# MB1297_Peripherals.net
KiCad netlist of a schematic drawn in Altium Designer
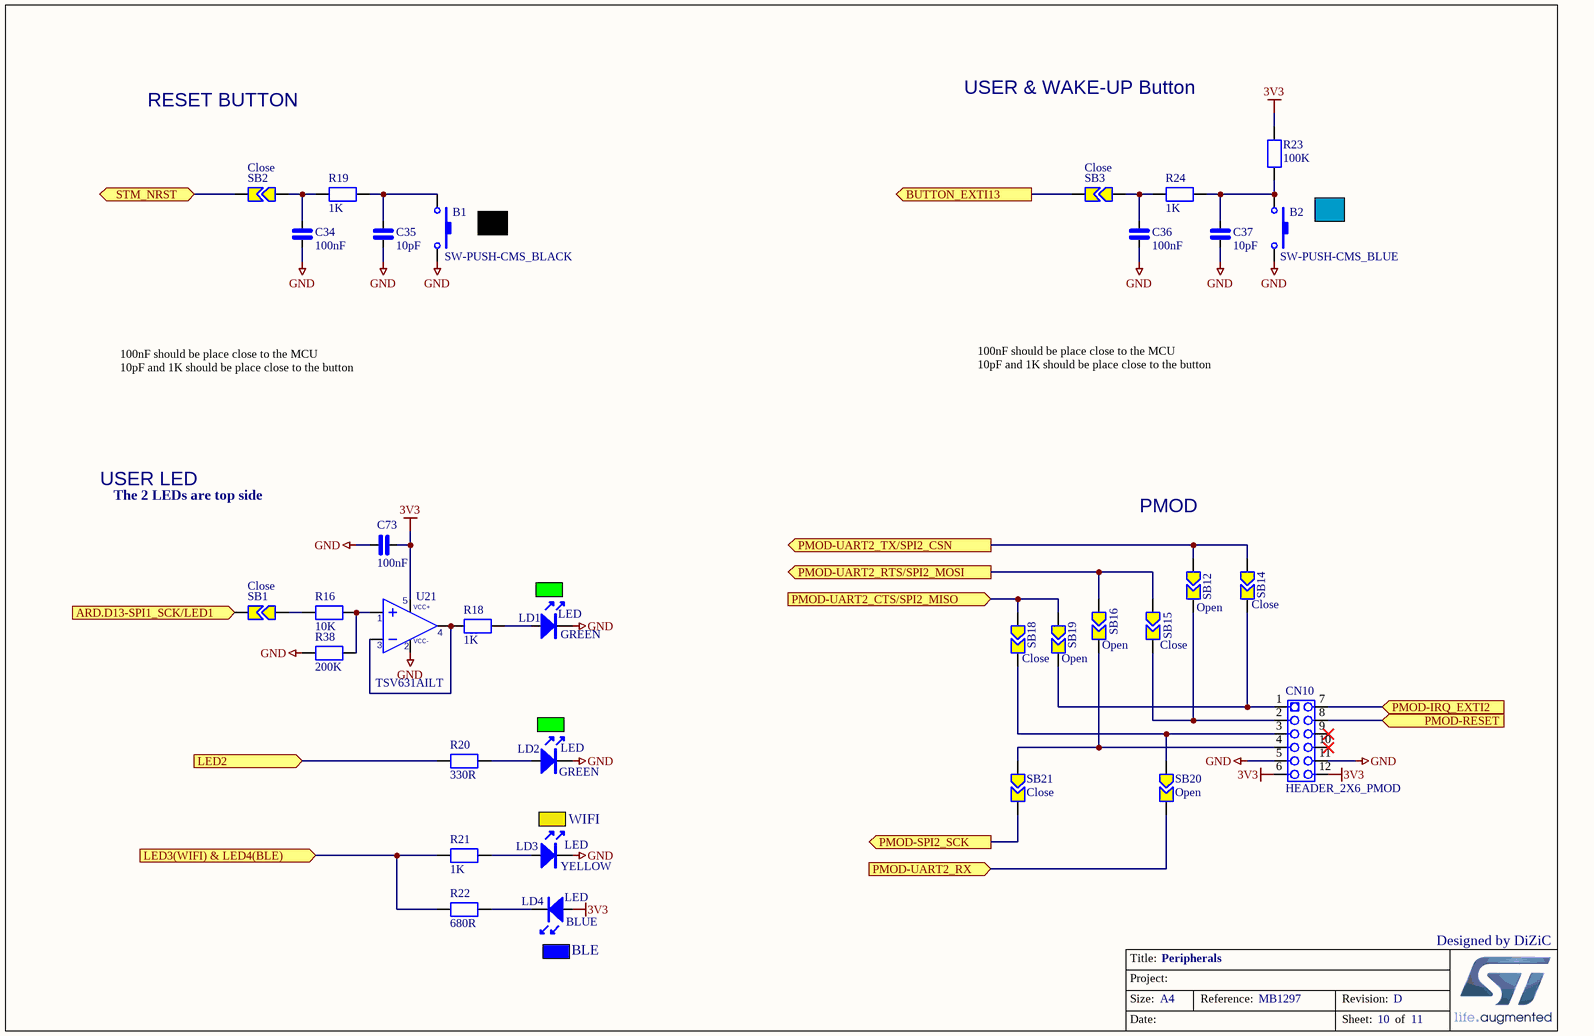
[diagram p0: MB1297_Peripherals.SchDoc]

(export (version "E")
  (design (tool "Eeschema 10.0.6"))
  (components
    (comp (ref "B1")
      (value "SW-PUSH-CMS_BLACK")
      (footprint "SWI_WEALTHMETAL_TD-0341_4P - BACK")
      (description "Push-button SMD")
      (libsource (lib "ST_Lib3D") (part "SW-PB_2"))
    )
    (comp (ref "B2")
      (value "SW-PUSH-CMS_BLUE")
      (footprint "SWI_WEALTHMETAL_TD-0341_4P - BLUE")
      (description "Push-button SMD")
      (libsource (lib "ST_Lib3D") (part "SW-PB_2"))
    )
    (comp (ref "C34")
      (value "100nF")
      (footprint "0402_CAP_NPOL")
      (description "Capacitor_not polarized")
      (libsource (lib "ST_Lib3D") (part "CAP_NPOL"))
    )
    (comp (ref "C35")
      (value "10pF")
      (footprint "0402_CAP_NPOL")
      (description "Capacitor_not polarized")
      (libsource (lib "ST_Lib3D") (part "CAP_NPOL"))
    )
    (comp (ref "C36")
      (value "100nF")
      (footprint "0402_CAP_NPOL")
      (description "Capacitor_not polarized")
      (libsource (lib "ST_Lib3D") (part "CAP_NPOL"))
    )
    (comp (ref "C37")
      (value "10pF")
      (footprint "0402_CAP_NPOL")
      (description "Capacitor_not polarized")
      (libsource (lib "ST_Lib3D") (part "CAP_NPOL"))
    )
    (comp (ref "C73")
      (value "100nF")
      (footprint "0402_CAP_NPOL")
      (description "Capacitor_not polarized")
      (libsource (lib "ST_Lib3D") (part "CAP_NPOL"))
    )
    (comp (ref "CN10")
      (value "HEADER_2X6_PMOD")
      (footprint "Header F 2x6x2.54 TH H PMOD")
      (description "PMOD Connector Warning Specific Pinout")
      (libsource (lib "ST_Lib3D") (part "HEADER_2X6_PMOD"))
    )
    (comp (ref "LD1")
      (value "LED")
      (footprint "0603_LED_GREEN")
      (description "Light-Emitting Diode")
      (fields (field (name "COLOR") "GREEN"))
      (libsource (lib "ST_Lib3D") (part "LED"))
    )
    (comp (ref "LD2")
      (value "LED")
      (footprint "0603_LED_GREEN")
      (description "Light-Emitting Diode")
      (fields (field (name "COLOR") "GREEN"))
      (libsource (lib "ST_Lib3D") (part "LED"))
    )
    (comp (ref "LD3")
      (value "LED")
      (footprint "0603_LED_Yellow")
      (description "Light-Emitting Diode")
      (fields (field (name "COLOR") "YELLOW"))
      (libsource (lib "ST_Lib3D") (part "LED"))
    )
    (comp (ref "LD4")
      (value "LED")
      (footprint "0603_LED_Blue")
      (description "Light-Emitting Diode")
      (fields (field (name "COLOR") "BLUE"))
      (libsource (lib "ST_Lib3D") (part "LED"))
    )
    (comp (ref "R16")
      (value "10K")
      (footprint "0402_RES")
      (description "Resistor")
      (libsource (lib "Lib3D_Altium10_Schlib") (part "RES"))
    )
    (comp (ref "R18")
      (value "1K")
      (footprint "0402_RES")
      (description "Resistor")
      (libsource (lib "Lib3D_Altium10_Schlib") (part "RES"))
    )
    (comp (ref "R19")
      (value "1K")
      (footprint "0402_RES")
      (description "Resistor")
      (libsource (lib "Lib3D_Altium10_Schlib") (part "RES"))
    )
    (comp (ref "R20")
      (value "330R")
      (footprint "0402_RES")
      (description "Resistor")
      (libsource (lib "Lib3D_Altium10_Schlib") (part "RES"))
    )
    (comp (ref "R21")
      (value "1K")
      (footprint "0402_RES")
      (description "Resistor")
      (libsource (lib "Lib3D_Altium10_Schlib") (part "RES"))
    )
    (comp (ref "R22")
      (value "680R")
      (footprint "0402_RES")
      (description "Resistor")
      (libsource (lib "Lib3D_Altium10_Schlib") (part "RES"))
    )
    (comp (ref "R23")
      (value "100K")
      (footprint "0402_RES")
      (description "Resistor")
      (libsource (lib "Lib3D_Altium10_Schlib") (part "RES"))
    )
    (comp (ref "R24")
      (value "1K")
      (footprint "0402_RES")
      (description "Resistor")
      (libsource (lib "Lib3D_Altium10_Schlib") (part "RES"))
    )
    (comp (ref "R38")
      (value "200K")
      (footprint "0402_RES")
      (description "Resistor")
      (libsource (lib "Lib3D_Altium10_Schlib") (part "RES"))
    )
    (comp (ref "SB1")
      (value "Close")
      (footprint "SB")
      (description "Solder Jumper")
      (fields (field (name "PUBLISHER") "Altium Limited"))
      (libsource (lib "Lib3D_Altium10_Schlib") (part "Strap2"))
    )
    (comp (ref "SB2")
      (value "Close")
      (footprint "SB")
      (description "Solder Jumper")
      (fields (field (name "PUBLISHER") "Altium Limited"))
      (libsource (lib "Lib3D_Altium10_Schlib") (part "Strap2"))
    )
    (comp (ref "SB3")
      (value "Close")
      (footprint "SB")
      (description "Solder Jumper")
      (fields (field (name "PUBLISHER") "Altium Limited"))
      (libsource (lib "Lib3D_Altium10_Schlib") (part "Strap2"))
    )
    (comp (ref "SB12")
      (value "Open")
      (footprint "SB")
      (description "Solder Jumper")
      (fields (field (name "PUBLISHER") "Altium Limited"))
      (libsource (lib "Lib3D_Altium10_Schlib") (part "Strap2"))
    )
    (comp (ref "SB14")
      (value "Close")
      (footprint "SB")
      (description "Solder Jumper")
      (fields (field (name "PUBLISHER") "Altium Limited"))
      (libsource (lib "Lib3D_Altium10_Schlib") (part "Strap2"))
    )
    (comp (ref "SB15")
      (value "Close")
      (footprint "SB")
      (description "Solder Jumper")
      (fields (field (name "PUBLISHER") "Altium Limited"))
      (libsource (lib "Lib3D_Altium10_Schlib") (part "Strap2"))
    )
    (comp (ref "SB16")
      (value "Open")
      (footprint "SB")
      (description "Solder Jumper")
      (fields (field (name "PUBLISHER") "Altium Limited"))
      (libsource (lib "Lib3D_Altium10_Schlib") (part "Strap2"))
    )
    (comp (ref "SB18")
      (value "Close")
      (footprint "SB")
      (description "Solder Jumper")
      (fields (field (name "PUBLISHER") "Altium Limited"))
      (libsource (lib "Lib3D_Altium10_Schlib") (part "Strap2"))
    )
    (comp (ref "SB19")
      (value "Open")
      (footprint "SB")
      (description "Solder Jumper")
      (fields (field (name "PUBLISHER") "Altium Limited"))
      (libsource (lib "Lib3D_Altium10_Schlib") (part "Strap2"))
    )
    (comp (ref "SB20")
      (value "Open")
      (footprint "SB")
      (description "Solder Jumper")
      (fields (field (name "PUBLISHER") "Altium Limited"))
      (libsource (lib "Lib3D_Altium10_Schlib") (part "Strap2"))
    )
    (comp (ref "SB21")
      (value "Close")
      (footprint "SB")
      (description "Solder Jumper")
      (fields (field (name "PUBLISHER") "Altium Limited"))
      (libsource (lib "Lib3D_Altium10_Schlib") (part "Strap2"))
    )
    (comp (ref "U21")
      (value "TSV631AILT")
      (footprint "ST_Lib3D:SOT23-5")
      (description "TSV631AILT  Rail-to-rail input/output, 60 µA, 880 kHz, 5 V CMOS  operational amplifiers")
      (libsource (lib "ST_Lib3D") (part "TSV631AILT"))
    )
  )
  (nets
    (net (code "1") (name "/ARD.D13-SPI1_SCK{slash}LED1") (class "Default")
      (node (ref "SB1") (pin "1") (pinfunction "1_1") (pintype "passive"))
    )
    (net (code "2") (name "/BUTTON_EXTI13") (class "Default")
      (node (ref "SB3") (pin "1") (pinfunction "1_1") (pintype "passive"))
    )
    (net (code "3") (name "/LED2") (class "Default")
      (node (ref "R20") (pin "1") (pinfunction "1_1") (pintype "passive"))
    )
    (net (code "4") (name "/LED3(WIFI) & LED4(BLE)") (class "Default")
      (node (ref "R21") (pin "1") (pinfunction "1_1") (pintype "passive"))
      (node (ref "R22") (pin "1") (pinfunction "1_1") (pintype "passive"))
    )
    (net (code "5") (name "/PMOD-IRQ_EXTI2") (class "Default")
      (node (ref "CN10") (pin "7") (pinfunction "7_7") (pintype "passive"))
    )
    (net (code "6") (name "/PMOD-RESET") (class "Default")
      (node (ref "CN10") (pin "8") (pinfunction "8_8") (pintype "passive"))
    )
    (net (code "7") (name "/PMOD-SPI2_SCK") (class "Default")
      (node (ref "SB21") (pin "1") (pinfunction "1_1") (pintype "passive"))
    )
    (net (code "8") (name "/PMOD-UART2_CTS{slash}SPI2_MISO") (class "Default")
      (node (ref "SB18") (pin "2") (pinfunction "2_2") (pintype "passive"))
      (node (ref "SB19") (pin "2") (pinfunction "2_2") (pintype "passive"))
    )
    (net (code "9") (name "/PMOD-UART2_RTS{slash}SPI2_MOSI") (class "Default")
      (node (ref "SB15") (pin "2") (pinfunction "2_2") (pintype "passive"))
      (node (ref "SB16") (pin "2") (pinfunction "2_2") (pintype "passive"))
    )
    (net (code "10") (name "/PMOD-UART2_RX") (class "Default")
      (node (ref "SB20") (pin "1") (pinfunction "1_1") (pintype "passive"))
    )
    (net (code "11") (name "/PMOD-UART2_TX{slash}SPI2_CSN") (class "Default")
      (node (ref "SB12") (pin "2") (pinfunction "2_2") (pintype "passive"))
      (node (ref "SB14") (pin "2") (pinfunction "2_2") (pintype "passive"))
    )
    (net (code "12") (name "/STM_NRST") (class "Default")
      (node (ref "SB2") (pin "1") (pinfunction "1_1") (pintype "passive"))
    )
    (net (code "13") (name "3V3") (class "Default")
      (node (ref "C73") (pin "1") (pinfunction "1_1") (pintype "passive"))
      (node (ref "CN10") (pin "12") (pinfunction "12_12") (pintype "passive"))
      (node (ref "CN10") (pin "6") (pinfunction "6_6") (pintype "passive"))
      (node (ref "LD4") (pin "A") (pinfunction "A_A") (pintype "passive"))
      (node (ref "R23") (pin "2") (pinfunction "2_2") (pintype "passive"))
      (node (ref "U21") (pin "5") (pinfunction "V+_5") (pintype "passive"))
    )
    (net (code "14") (name "GND") (class "Default")
      (node (ref "B1") (pin "2") (pinfunction "2_2") (pintype "passive"))
      (node (ref "B2") (pin "2") (pinfunction "2_2") (pintype "passive"))
      (node (ref "C34") (pin "2") (pinfunction "2_2") (pintype "passive"))
      (node (ref "C35") (pin "2") (pinfunction "2_2") (pintype "passive"))
      (node (ref "C36") (pin "2") (pinfunction "2_2") (pintype "passive"))
      (node (ref "C37") (pin "2") (pinfunction "2_2") (pintype "passive"))
      (node (ref "C73") (pin "2") (pinfunction "2_2") (pintype "passive"))
      (node (ref "CN10") (pin "11") (pinfunction "11_11") (pintype "passive"))
      (node (ref "CN10") (pin "5") (pinfunction "5_5") (pintype "passive"))
      (node (ref "LD1") (pin "K") (pinfunction "K_K") (pintype "passive"))
      (node (ref "LD2") (pin "K") (pinfunction "K_K") (pintype "passive"))
      (node (ref "LD3") (pin "K") (pinfunction "K_K") (pintype "passive"))
      (node (ref "R38") (pin "1") (pinfunction "1_1") (pintype "passive"))
      (node (ref "U21") (pin "2") (pinfunction "V-_2") (pintype "passive"))
    )
    (net (code "15") (name "Net-(B1-Pad1)") (class "Default")
      (node (ref "B1") (pin "1") (pinfunction "1_1") (pintype "passive"))
      (node (ref "C35") (pin "1") (pinfunction "1_1") (pintype "passive"))
      (node (ref "R19") (pin "2") (pinfunction "2_2") (pintype "passive"))
    )
    (net (code "16") (name "Net-(B2-Pad1)") (class "Default")
      (node (ref "B2") (pin "1") (pinfunction "1_1") (pintype "passive"))
      (node (ref "C37") (pin "1") (pinfunction "1_1") (pintype "passive"))
      (node (ref "R23") (pin "1") (pinfunction "1_1") (pintype "passive"))
      (node (ref "R24") (pin "2") (pinfunction "2_2") (pintype "passive"))
    )
    (net (code "17") (name "Net-(C34-Pad1)") (class "Default")
      (node (ref "C34") (pin "1") (pinfunction "1_1") (pintype "passive"))
      (node (ref "R19") (pin "1") (pinfunction "1_1") (pintype "passive"))
      (node (ref "SB2") (pin "2") (pinfunction "2_2") (pintype "passive"))
    )
    (net (code "18") (name "Net-(C36-Pad1)") (class "Default")
      (node (ref "C36") (pin "1") (pinfunction "1_1") (pintype "passive"))
      (node (ref "R24") (pin "1") (pinfunction "1_1") (pintype "passive"))
      (node (ref "SB3") (pin "2") (pinfunction "2_2") (pintype "passive"))
    )
    (net (code "19") (name "Net-(CN10-Pad1)") (class "Default")
      (node (ref "CN10") (pin "1") (pinfunction "1_1") (pintype "passive"))
      (node (ref "SB14") (pin "1") (pinfunction "1_1") (pintype "passive"))
      (node (ref "SB19") (pin "1") (pinfunction "1_1") (pintype "passive"))
    )
    (net (code "20") (name "Net-(CN10-Pad2)") (class "Default")
      (node (ref "CN10") (pin "2") (pinfunction "2_2") (pintype "passive"))
      (node (ref "SB12") (pin "1") (pinfunction "1_1") (pintype "passive"))
      (node (ref "SB15") (pin "1") (pinfunction "1_1") (pintype "passive"))
    )
    (net (code "21") (name "Net-(CN10-Pad3)") (class "Default")
      (node (ref "CN10") (pin "3") (pinfunction "3_3") (pintype "passive"))
      (node (ref "SB18") (pin "1") (pinfunction "1_1") (pintype "passive"))
      (node (ref "SB20") (pin "2") (pinfunction "2_2") (pintype "passive"))
    )
    (net (code "22") (name "Net-(CN10-Pad4)") (class "Default")
      (node (ref "CN10") (pin "4") (pinfunction "4_4") (pintype "passive"))
      (node (ref "SB16") (pin "1") (pinfunction "1_1") (pintype "passive"))
      (node (ref "SB21") (pin "2") (pinfunction "2_2") (pintype "passive"))
    )
    (net (code "23") (name "Net-(LD1-PadA)") (class "Default")
      (node (ref "LD1") (pin "A") (pinfunction "A_A") (pintype "passive"))
      (node (ref "R18") (pin "2") (pinfunction "2_2") (pintype "passive"))
    )
    (net (code "24") (name "Net-(LD2-PadA)") (class "Default")
      (node (ref "LD2") (pin "A") (pinfunction "A_A") (pintype "passive"))
      (node (ref "R20") (pin "2") (pinfunction "2_2") (pintype "passive"))
    )
    (net (code "25") (name "Net-(LD3-PadA)") (class "Default")
      (node (ref "LD3") (pin "A") (pinfunction "A_A") (pintype "passive"))
      (node (ref "R21") (pin "2") (pinfunction "2_2") (pintype "passive"))
    )
    (net (code "26") (name "Net-(LD4-PadK)") (class "Default")
      (node (ref "LD4") (pin "K") (pinfunction "K_K") (pintype "passive"))
      (node (ref "R22") (pin "2") (pinfunction "2_2") (pintype "passive"))
    )
    (net (code "27") (name "Net-(R16-Pad1)") (class "Default")
      (node (ref "R16") (pin "1") (pinfunction "1_1") (pintype "passive"))
      (node (ref "SB1") (pin "2") (pinfunction "2_2") (pintype "passive"))
    )
    (net (code "28") (name "Net-(U21-IN+)") (class "Default")
      (node (ref "R16") (pin "2") (pinfunction "2_2") (pintype "passive"))
      (node (ref "R38") (pin "2") (pinfunction "2_2") (pintype "passive"))
      (node (ref "U21") (pin "1") (pinfunction "IN+_1") (pintype "passive"))
    )
    (net (code "29") (name "Net-(U21-IN-)") (class "Default")
      (node (ref "R18") (pin "1") (pinfunction "1_1") (pintype "passive"))
      (node (ref "U21") (pin "3") (pinfunction "IN-_3") (pintype "passive"))
      (node (ref "U21") (pin "4") (pinfunction "OUT_4") (pintype "passive"))
    )
    (net (code "30") (name "unconnected-(CN10-Pad9)") (class "Default")
      (node (ref "CN10") (pin "9") (pinfunction "9_9") (pintype "passive+no_connect"))
    )
    (net (code "31") (name "unconnected-(CN10-Pad10)") (class "Default")
      (node (ref "CN10") (pin "10") (pinfunction "10_10") (pintype "passive+no_connect"))
    )
  )
)
